# v0_5_1.net
KiCad netlist of a schematic drawn in EAGLE
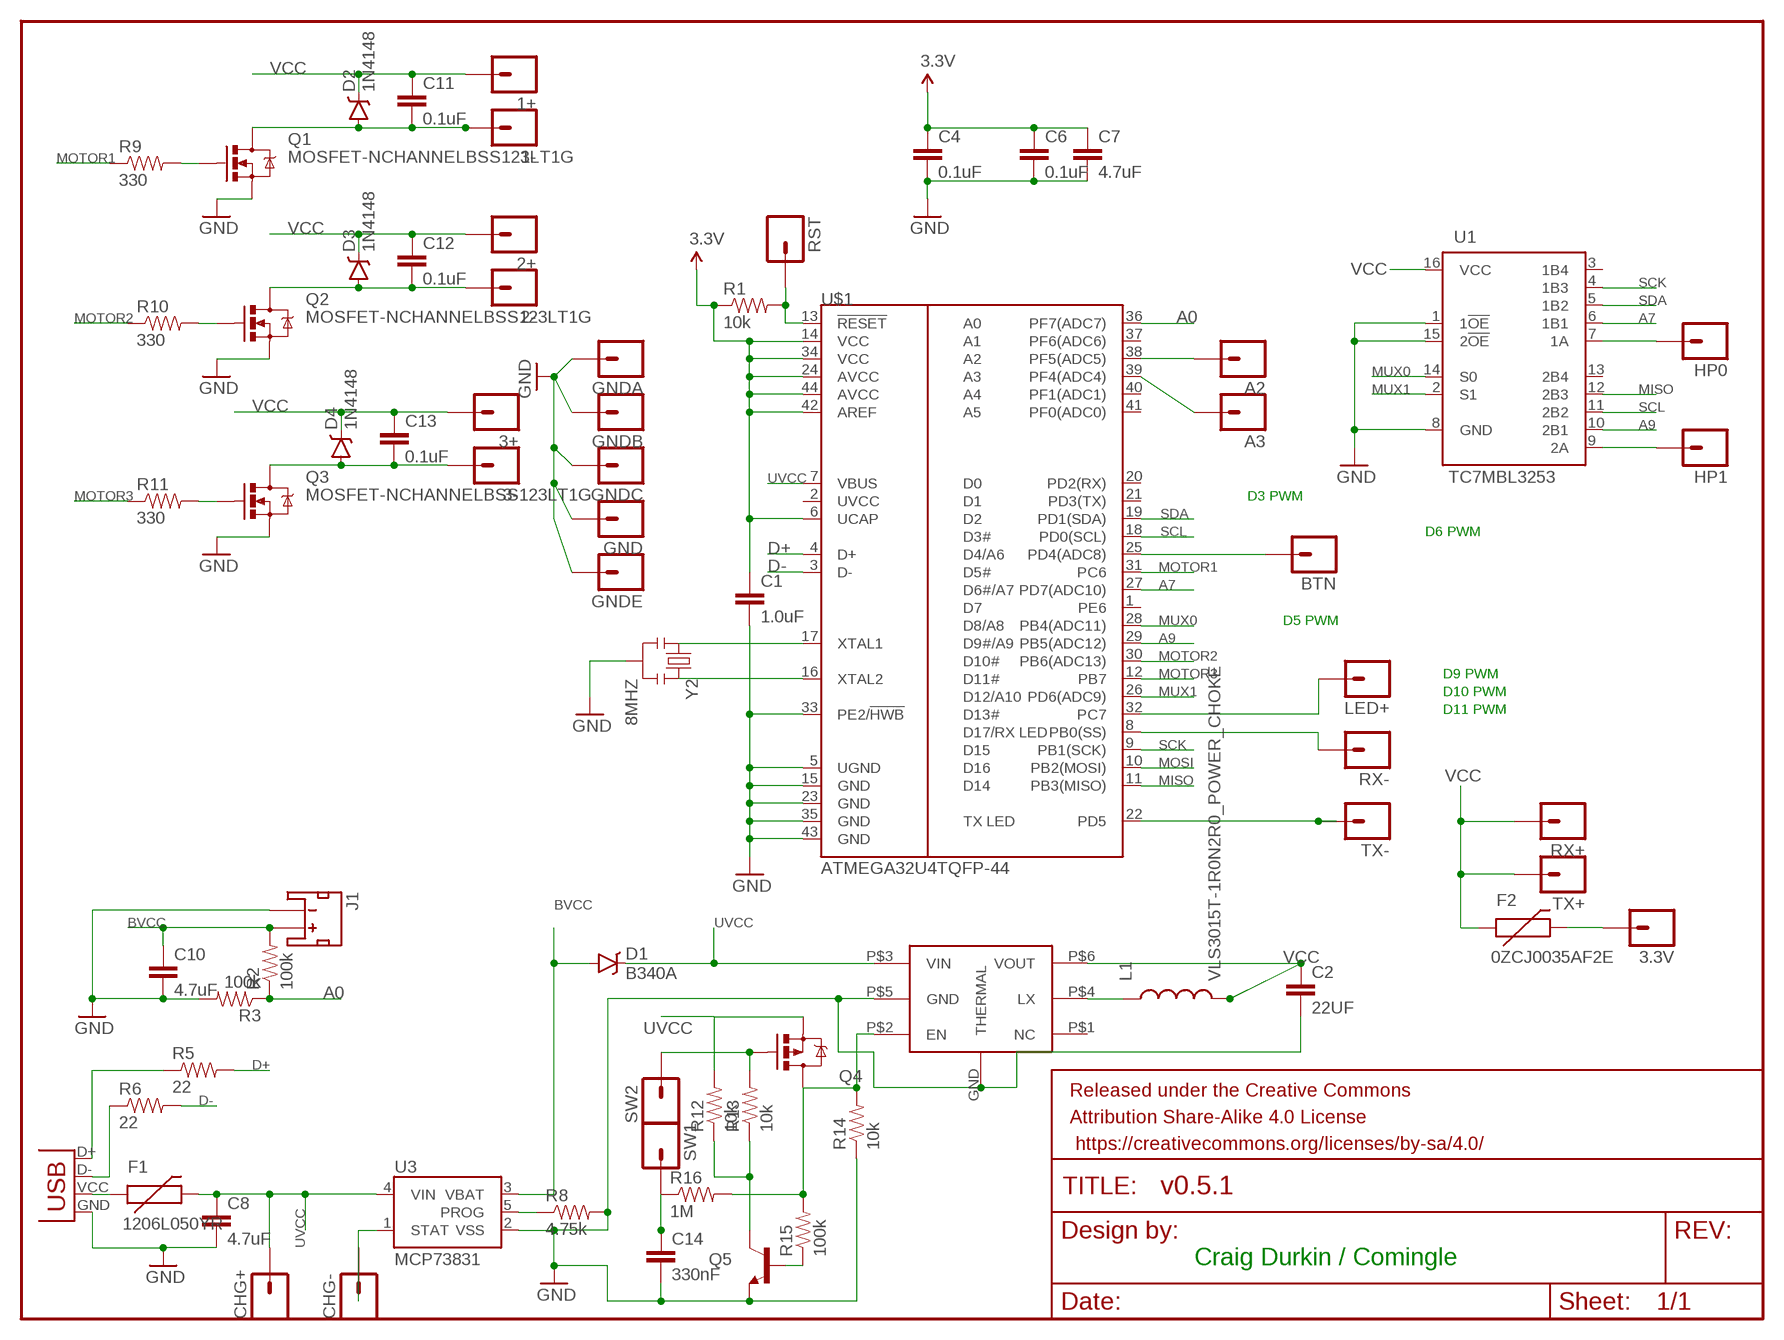
[diagram p0: schematic, sheet 1]

(export (version "E")
  (design (tool "Eeschema 10.0.6"))
  (components
    (comp (ref "1+")
      (value "M01PTH")
      (footprint "eagle-import:1X01")
      (libsource (lib "eagle-import") (part "M01PTH"))
    )
    (comp (ref "1-")
      (value "M01PTH")
      (footprint "eagle-import:1X01")
      (libsource (lib "eagle-import") (part "M01PTH"))
    )
    (comp (ref "2+")
      (value "M01PTH")
      (footprint "eagle-import:1X01")
      (libsource (lib "eagle-import") (part "M01PTH"))
    )
    (comp (ref "2-")
      (value "M01PTH")
      (footprint "eagle-import:1X01")
      (libsource (lib "eagle-import") (part "M01PTH"))
    )
    (comp (ref "3+")
      (value "M01PTH")
      (footprint "eagle-import:1X01")
      (libsource (lib "eagle-import") (part "M01PTH"))
    )
    (comp (ref "3-")
      (value "M01PTH")
      (footprint "eagle-import:1X01")
      (libsource (lib "eagle-import") (part "M01PTH"))
    )
    (comp (ref "3.3V")
      (value "M01PTH")
      (footprint "eagle-import:1X01")
      (libsource (lib "eagle-import") (part "M01PTH"))
    )
    (comp (ref "A2")
      (value "M01PTH")
      (footprint "eagle-import:1X01")
      (libsource (lib "eagle-import") (part "M01PTH"))
    )
    (comp (ref "A3")
      (value "M01PTH")
      (footprint "eagle-import:1X01")
      (libsource (lib "eagle-import") (part "M01PTH"))
    )
    (comp (ref "BTN")
      (value "M01PTH")
      (footprint "eagle-import:1X01")
      (libsource (lib "eagle-import") (part "M01PTH"))
    )
    (comp (ref "C1")
      (value "1.0uF")
      (footprint "eagle-import:0603-CAP")
      (libsource (lib "eagle-import") (part "CAP0603-CAP"))
    )
    (comp (ref "C2")
      (value "22UF")
      (footprint "eagle-import:0805")
      (libsource (lib "eagle-import") (part "v0.4.6_CAP0805"))
    )
    (comp (ref "C4")
      (value "0.1uF")
      (footprint "eagle-import:0603-CAP")
      (libsource (lib "eagle-import") (part "SparkFun-Passives_CAP0603-CAP"))
    )
    (comp (ref "C6")
      (value "0.1uF")
      (footprint "eagle-import:0603-CAP")
      (libsource (lib "eagle-import") (part "SparkFun-Passives_CAP0603-CAP"))
    )
    (comp (ref "C7")
      (value "4.7uF")
      (footprint "eagle-import:0603-CAP")
      (libsource (lib "eagle-import") (part "SparkFun-Passives_CAP0603-CAP"))
    )
    (comp (ref "C8")
      (value "4.7uF")
      (footprint "eagle-import:1206")
      (libsource (lib "eagle-import") (part "SparkFun-Passives_CAP1206"))
    )
    (comp (ref "C10")
      (value "4.7uF")
      (footprint "eagle-import:1206")
      (libsource (lib "eagle-import") (part "SparkFun-Passives_CAP1206"))
    )
    (comp (ref "C11")
      (value "0.1uF")
      (footprint "eagle-import:0603-CAP")
      (libsource (lib "eagle-import") (part "CAP0603-CAP"))
    )
    (comp (ref "C12")
      (value "0.1uF")
      (footprint "eagle-import:0603-CAP")
      (libsource (lib "eagle-import") (part "CAP0603-CAP"))
    )
    (comp (ref "C13")
      (value "0.1uF")
      (footprint "eagle-import:0603-CAP")
      (libsource (lib "eagle-import") (part "CAP0603-CAP"))
    )
    (comp (ref "C14")
      (value "330nF")
      (footprint "eagle-import:0603-CAP")
      (libsource (lib "eagle-import") (part "CAP0603-CAP"))
    )
    (comp (ref "CHG+")
      (value "M01PTH")
      (footprint "eagle-import:1X01")
      (libsource (lib "eagle-import") (part "M01PTH"))
    )
    (comp (ref "CHG-")
      (value "M01PTH")
      (footprint "eagle-import:1X01")
      (libsource (lib "eagle-import") (part "M01PTH"))
    )
    (comp (ref "D1")
      (value "B340A")
      (footprint "eagle-import:SMA-DIODE")
      (libsource (lib "eagle-import") (part "DIODE-SCHOTTKY-B340A"))
    )
    (comp (ref "D2")
      (value "1N4148")
      (footprint "eagle-import:SOD-323")
      (libsource (lib "eagle-import") (part "BAT20JFILM"))
    )
    (comp (ref "D3")
      (value "1N4148")
      (footprint "eagle-import:SOD-323")
      (libsource (lib "eagle-import") (part "BAT20JFILM"))
    )
    (comp (ref "D4")
      (value "1N4148")
      (footprint "eagle-import:SOD-323")
      (libsource (lib "eagle-import") (part "BAT20JFILM"))
    )
    (comp (ref "F1")
      (value "1206L050YR")
      (footprint "eagle-import:PTC-1206")
      (libsource (lib "eagle-import") (part "PTCSMD"))
    )
    (comp (ref "F2")
      (value "0ZCJ0035AF2E")
      (footprint "eagle-import:PTC-1206")
      (libsource (lib "eagle-import") (part "PTCSMD"))
    )
    (comp (ref "FRAME1")
      (value "FRAME-LETTER")
      (footprint "eagle-import:CREATIVE_COMMONS")
      (libsource (lib "eagle-import") (part "FRAME-LETTER"))
    )
    (comp (ref "GND")
      (value "M01PTH")
      (footprint "eagle-import:1X01")
      (libsource (lib "eagle-import") (part "M01PTH"))
    )
    (comp (ref "GNDA")
      (value "M01PTH")
      (footprint "eagle-import:1X01")
      (libsource (lib "eagle-import") (part "M01PTH"))
    )
    (comp (ref "GNDB")
      (value "M01PTH")
      (footprint "eagle-import:1X01")
      (libsource (lib "eagle-import") (part "M01PTH"))
    )
    (comp (ref "GNDC")
      (value "M01PTH")
      (footprint "eagle-import:1X01")
      (libsource (lib "eagle-import") (part "M01PTH"))
    )
    (comp (ref "GNDE")
      (value "M01PTH")
      (footprint "eagle-import:1X01")
      (libsource (lib "eagle-import") (part "M01PTH"))
    )
    (comp (ref "HP0")
      (value "M01PTH")
      (footprint "eagle-import:1X01")
      (libsource (lib "eagle-import") (part "M01PTH"))
    )
    (comp (ref "HP1")
      (value "M01PTH")
      (footprint "eagle-import:1X01")
      (libsource (lib "eagle-import") (part "M01PTH"))
    )
    (comp (ref "J1")
      (value "JST_2MM_MALE")
      (footprint "eagle-import:JST-2-SMD")
      (libsource (lib "eagle-import") (part "JST_2MM_MALE"))
    )
    (comp (ref "JP4")
      (value "USBMICROB-GCT-USB3075")
      (footprint "eagle-import:USB-MICROB-GCT-USB3075")
      (libsource (lib "eagle-import") (part "USBMICROB-GCT-USB3075"))
    )
    (comp (ref "L1")
      (value "VLS3015T-1R0N2R0_POWER_CHOKE")
      (footprint "eagle-import:3MM_POWER_CHOKE")
      (libsource (lib "eagle-import") (part "VLS3015T-1R0N2R0_POWER_CHOKE"))
    )
    (comp (ref "LED+")
      (value "M01PTH")
      (footprint "eagle-import:1X01")
      (libsource (lib "eagle-import") (part "M01PTH"))
    )
    (comp (ref "Q1")
      (value "MOSFET-NCHANNELBSS123LT1G")
      (footprint "eagle-import:SOT23-3")
      (libsource (lib "eagle-import") (part "MOSFET-NCHANNELBSS123LT1G"))
    )
    (comp (ref "Q2")
      (value "MOSFET-NCHANNELBSS123LT1G")
      (footprint "eagle-import:SOT23-3")
      (libsource (lib "eagle-import") (part "MOSFET-NCHANNELBSS123LT1G"))
    )
    (comp (ref "Q3")
      (value "MOSFET-NCHANNELBSS123LT1G")
      (footprint "eagle-import:SOT23-3")
      (libsource (lib "eagle-import") (part "MOSFET-NCHANNELBSS123LT1G"))
    )
    (comp (ref "Q4")
      (value "NTS2101PT1G")
      (footprint "eagle-import:SOT323")
      (libsource (lib "eagle-import") (part "MOSFET-PCHANNELSOT323"))
    )
    (comp (ref "Q5")
      (value "MMBT2222A")
      (footprint "eagle-import:SOT23-3")
      (libsource (lib "eagle-import") (part "TRANSISTOR_NPNMMBT2222A"))
    )
    (comp (ref "R1")
      (value "10k")
      (footprint "eagle-import:0603-RES")
      (libsource (lib "eagle-import") (part "RESISTOR0603-RES"))
    )
    (comp (ref "R2")
      (value "100k")
      (footprint "eagle-import:0603-RES")
      (libsource (lib "eagle-import") (part "RESISTOR0603-RES"))
    )
    (comp (ref "R3")
      (value "100k")
      (footprint "eagle-import:0603-RES")
      (libsource (lib "eagle-import") (part "RESISTOR0603-RES"))
    )
    (comp (ref "R5")
      (value "22")
      (footprint "eagle-import:0603-RES")
      (libsource (lib "eagle-import") (part "RESISTOR0603-RES"))
    )
    (comp (ref "R6")
      (value "22")
      (footprint "eagle-import:0603-RES")
      (libsource (lib "eagle-import") (part "RESISTOR0603-RES"))
    )
    (comp (ref "R8")
      (value "4.75k")
      (footprint "eagle-import:0603-RES")
      (libsource (lib "eagle-import") (part "RESISTOR0603-RES"))
    )
    (comp (ref "R9")
      (value "330")
      (footprint "eagle-import:0603-RES")
      (libsource (lib "eagle-import") (part "RESISTOR0603-RES"))
    )
    (comp (ref "R10")
      (value "330")
      (footprint "eagle-import:0603-RES")
      (libsource (lib "eagle-import") (part "RESISTOR0603-RES"))
    )
    (comp (ref "R11")
      (value "330")
      (footprint "eagle-import:0603-RES")
      (libsource (lib "eagle-import") (part "RESISTOR0603-RES"))
    )
    (comp (ref "R12")
      (value "10k")
      (footprint "eagle-import:0603-RES")
      (libsource (lib "eagle-import") (part "RESISTOR0603-RES"))
    )
    (comp (ref "R13")
      (value "10k")
      (footprint "eagle-import:0603-RES")
      (libsource (lib "eagle-import") (part "RESISTOR0603-RES"))
    )
    (comp (ref "R14")
      (value "10k")
      (footprint "eagle-import:0603-RES")
      (libsource (lib "eagle-import") (part "RESISTOR0603-RES"))
    )
    (comp (ref "R15")
      (value "100k")
      (footprint "eagle-import:0603-RES")
      (libsource (lib "eagle-import") (part "RESISTOR0603-RES"))
    )
    (comp (ref "R16")
      (value "1M")
      (footprint "eagle-import:0603-RES")
      (libsource (lib "eagle-import") (part "RESISTOR0603-RES"))
    )
    (comp (ref "RST")
      (value "M01PTH")
      (footprint "eagle-import:1X01")
      (libsource (lib "eagle-import") (part "M01PTH"))
    )
    (comp (ref "RX+")
      (value "M01PTH")
      (footprint "eagle-import:1X01")
      (libsource (lib "eagle-import") (part "M01PTH"))
    )
    (comp (ref "RX-")
      (value "M01PTH")
      (footprint "eagle-import:1X01")
      (libsource (lib "eagle-import") (part "M01PTH"))
    )
    (comp (ref "SW1")
      (value "M01PTH")
      (footprint "eagle-import:1X01")
      (libsource (lib "eagle-import") (part "M01PTH"))
    )
    (comp (ref "SW2")
      (value "M01PTH")
      (footprint "eagle-import:1X01")
      (libsource (lib "eagle-import") (part "M01PTH"))
    )
    (comp (ref "TX+")
      (value "M01PTH")
      (footprint "eagle-import:1X01")
      (libsource (lib "eagle-import") (part "M01PTH"))
    )
    (comp (ref "TX-")
      (value "M01PTH")
      (footprint "eagle-import:1X01")
      (libsource (lib "eagle-import") (part "M01PTH"))
    )
    (comp (ref "U$1")
      (value "ATMEGA32U4TQFP-44")
      (footprint "eagle-import:TQFP44")
      (libsource (lib "eagle-import") (part "ATMEGA32U4TQFP-44"))
    )
    (comp (ref "U$3")
      (value "SC189")
      (footprint "eagle-import:MLPD-UT6")
      (libsource (lib "eagle-import") (part "SC189"))
    )
    (comp (ref "U1")
      (value "TC7MBL3253")
      (footprint "eagle-import:SSOP16-PRACTICE")
      (libsource (lib "eagle-import") (part "TC7MBL3253"))
    )
    (comp (ref "U3")
      (value "MCP73831")
      (footprint "eagle-import:SOT23-5")
      (libsource (lib "eagle-import") (part "MCP73831"))
    )
    (comp (ref "Y2")
      (value "8MHZ")
      (footprint "eagle-import:RESONATOR-SMD")
      (libsource (lib "eagle-import") (part "RESONATOR8MHZ"))
    )
  )
  (nets
    (net (code "1") (name "/A0") (class "Default")
      (node (ref "R2") (pin "1") (pinfunction "1_1") (pintype "passive"))
      (node (ref "R3") (pin "1") (pinfunction "1_1") (pintype "passive"))
      (node (ref "U$1") (pin "36") (pinfunction "PF7(ADC7)_36") (pintype "bidirectional"))
    )
    (net (code "2") (name "/A7") (class "Default")
      (node (ref "U$1") (pin "27") (pinfunction "PD7(ADC10)_27") (pintype "bidirectional"))
      (node (ref "U1") (pin "6") (pinfunction "1B1_6") (pintype "bidirectional"))
    )
    (net (code "3") (name "/A9") (class "Default")
      (node (ref "U$1") (pin "29") (pinfunction "PB5(ADC12)_29") (pintype "bidirectional"))
      (node (ref "U1") (pin "10") (pinfunction "2B1_10") (pintype "bidirectional"))
    )
    (net (code "4") (name "/BVCC") (class "Default")
      (node (ref "C10") (pin "1") (pinfunction "1_1") (pintype "passive"))
      (node (ref "D1") (pin "A") (pinfunction "A_A") (pintype "passive"))
      (node (ref "J1") (pin "2") (pinfunction "+_2") (pintype "bidirectional"))
      (node (ref "R2") (pin "2") (pinfunction "2_2") (pintype "passive"))
      (node (ref "U3") (pin "3") (pinfunction "VBAT_3") (pintype "power_in"))
    )
    (net (code "5") (name "/D+") (class "Default")
      (node (ref "R5") (pin "2") (pinfunction "2_2") (pintype "passive"))
      (node (ref "U$1") (pin "4") (pinfunction "D+_4") (pintype "bidirectional"))
    )
    (net (code "6") (name "/D-") (class "Default")
      (node (ref "R6") (pin "2") (pinfunction "2_2") (pintype "passive"))
      (node (ref "U$1") (pin "3") (pinfunction "D-_3") (pintype "bidirectional"))
    )
    (net (code "7") (name "/MISO") (class "Default")
      (node (ref "U$1") (pin "11") (pinfunction "PB3(MISO)_11") (pintype "bidirectional"))
      (node (ref "U1") (pin "12") (pinfunction "2B3_12") (pintype "bidirectional"))
    )
    (net (code "8") (name "/MOSI") (class "Default")
      (node (ref "U$1") (pin "10") (pinfunction "PB2(MOSI)_10") (pintype "bidirectional"))
    )
    (net (code "9") (name "/MOTOR1") (class "Default")
      (node (ref "R9") (pin "1") (pinfunction "1_1") (pintype "passive"))
      (node (ref "U$1") (pin "31") (pinfunction "PC6_31") (pintype "bidirectional"))
    )
    (net (code "10") (name "/MOTOR2") (class "Default")
      (node (ref "R10") (pin "1") (pinfunction "1_1") (pintype "passive"))
      (node (ref "U$1") (pin "30") (pinfunction "PB6(ADC13)_30") (pintype "bidirectional"))
    )
    (net (code "11") (name "/MOTOR3") (class "Default")
      (node (ref "R11") (pin "1") (pinfunction "1_1") (pintype "passive"))
      (node (ref "U$1") (pin "12") (pinfunction "PB7_12") (pintype "bidirectional"))
    )
    (net (code "12") (name "/MUX0") (class "Default")
      (node (ref "U$1") (pin "28") (pinfunction "PB4(ADC11)_28") (pintype "bidirectional"))
      (node (ref "U1") (pin "14") (pinfunction "S0_14") (pintype "bidirectional"))
    )
    (net (code "13") (name "/MUX1") (class "Default")
      (node (ref "U$1") (pin "26") (pinfunction "PD6(ADC9)_26") (pintype "bidirectional"))
      (node (ref "U1") (pin "2") (pinfunction "S1_2") (pintype "bidirectional"))
    )
    (net (code "14") (name "/SCK") (class "Default")
      (node (ref "U$1") (pin "9") (pinfunction "PB1(SCK)_9") (pintype "bidirectional"))
      (node (ref "U1") (pin "4") (pinfunction "1B3_4") (pintype "bidirectional"))
    )
    (net (code "15") (name "/SCL") (class "Default")
      (node (ref "U$1") (pin "18") (pinfunction "PD0(SCL)_18") (pintype "bidirectional"))
      (node (ref "U1") (pin "11") (pinfunction "2B2_11") (pintype "bidirectional"))
    )
    (net (code "16") (name "/SDA") (class "Default")
      (node (ref "U$1") (pin "19") (pinfunction "PD1(SDA)_19") (pintype "bidirectional"))
      (node (ref "U1") (pin "5") (pinfunction "1B2_5") (pintype "bidirectional"))
    )
    (net (code "17") (name "/UVCC") (class "Default")
      (node (ref "C8") (pin "1") (pinfunction "1_1") (pintype "passive"))
      (node (ref "CHG+") (pin "1") (pinfunction "1_1") (pintype "passive"))
      (node (ref "D1") (pin "C") (pinfunction "C_C") (pintype "passive"))
      (node (ref "F1") (pin "2") (pinfunction "2_2") (pintype "bidirectional"))
      (node (ref "Q4") (pin "2") (pinfunction "S_2") (pintype "passive"))
      (node (ref "R12") (pin "2") (pinfunction "2_2") (pintype "passive"))
      (node (ref "U$1") (pin "7") (pinfunction "VBUS_7") (pintype "bidirectional"))
      (node (ref "U$3") (pin "P$3") (pinfunction "VIN_P$3") (pintype "power_in"))
      (node (ref "U3") (pin "4") (pinfunction "VIN_4") (pintype "power_in"))
    )
    (net (code "18") (name "3.3V") (class "Default")
      (node (ref "1+") (pin "1") (pinfunction "1_1") (pintype "passive"))
      (node (ref "2+") (pin "1") (pinfunction "1_1") (pintype "passive"))
      (node (ref "3+") (pin "1") (pinfunction "1_1") (pintype "passive"))
      (node (ref "C1") (pin "1") (pinfunction "1_1") (pintype "passive"))
      (node (ref "C11") (pin "1") (pinfunction "1_1") (pintype "passive"))
      (node (ref "C12") (pin "1") (pinfunction "1_1") (pintype "passive"))
      (node (ref "C13") (pin "1") (pinfunction "1_1") (pintype "passive"))
      (node (ref "C2") (pin "1") (pinfunction "1_1") (pintype "passive"))
      (node (ref "C4") (pin "1") (pinfunction "1_1") (pintype "passive"))
      (node (ref "C6") (pin "1") (pinfunction "1_1") (pintype "passive"))
      (node (ref "C7") (pin "1") (pinfunction "1_1") (pintype "passive"))
      (node (ref "D2") (pin "C") (pinfunction "C_C") (pintype "passive"))
      (node (ref "D3") (pin "C") (pinfunction "C_C") (pintype "passive"))
      (node (ref "D4") (pin "C") (pinfunction "C_C") (pintype "passive"))
      (node (ref "F2") (pin "1") (pinfunction "1_1") (pintype "bidirectional"))
      (node (ref "L1") (pin "2") (pinfunction "2_2") (pintype "passive"))
      (node (ref "R1") (pin "1") (pinfunction "1_1") (pintype "passive"))
      (node (ref "RX+") (pin "1") (pinfunction "1_1") (pintype "passive"))
      (node (ref "TX+") (pin "1") (pinfunction "1_1") (pintype "passive"))
      (node (ref "U$1") (pin "14") (pinfunction "VCC_14") (pintype "bidirectional"))
      (node (ref "U$1") (pin "24") (pinfunction "AVCC_24") (pintype "bidirectional"))
      (node (ref "U$1") (pin "34") (pinfunction "VCC_34") (pintype "bidirectional"))
      (node (ref "U$1") (pin "42") (pinfunction "AREF_42") (pintype "bidirectional"))
      (node (ref "U$1") (pin "44") (pinfunction "AVCC_44") (pintype "bidirectional"))
      (node (ref "U$1") (pin "6") (pinfunction "UCAP_6") (pintype "bidirectional"))
      (node (ref "U$3") (pin "P$6") (pinfunction "VOUT_P$6") (pintype "output"))
      (node (ref "U1") (pin "16") (pinfunction "VCC_16") (pintype "power_in"))
    )
    (net (code "19") (name "GND") (class "Default")
      (node (ref "C1") (pin "2") (pinfunction "2_2") (pintype "passive"))
      (node (ref "C10") (pin "2") (pinfunction "2_2") (pintype "passive"))
      (node (ref "C14") (pin "2") (pinfunction "2_2") (pintype "passive"))
      (node (ref "C2") (pin "2") (pinfunction "2_2") (pintype "passive"))
      (node (ref "C4") (pin "2") (pinfunction "2_2") (pintype "passive"))
      (node (ref "C6") (pin "2") (pinfunction "2_2") (pintype "passive"))
      (node (ref "C7") (pin "2") (pinfunction "2_2") (pintype "passive"))
      (node (ref "C8") (pin "2") (pinfunction "2_2") (pintype "passive"))
      (node (ref "GND") (pin "1") (pinfunction "1_1") (pintype "passive"))
      (node (ref "GNDA") (pin "1") (pinfunction "1_1") (pintype "passive"))
      (node (ref "GNDB") (pin "1") (pinfunction "1_1") (pintype "passive"))
      (node (ref "GNDC") (pin "1") (pinfunction "1_1") (pintype "passive"))
      (node (ref "GNDE") (pin "1") (pinfunction "1_1") (pintype "passive"))
      (node (ref "J1") (pin "1") (pinfunction "-_1") (pintype "bidirectional"))
      (node (ref "JP4") (pin "GND") (pinfunction "GND_GND") (pintype "bidirectional"))
      (node (ref "Q1") (pin "2") (pinfunction "S_2") (pintype "passive"))
      (node (ref "Q2") (pin "2") (pinfunction "S_2") (pintype "passive"))
      (node (ref "Q3") (pin "2") (pinfunction "S_2") (pintype "passive"))
      (node (ref "Q5") (pin "2") (pinfunction "E_2") (pintype "passive"))
      (node (ref "R14") (pin "1") (pinfunction "1_1") (pintype "passive"))
      (node (ref "R3") (pin "2") (pinfunction "2_2") (pintype "passive"))
      (node (ref "R8") (pin "2") (pinfunction "2_2") (pintype "passive"))
      (node (ref "U$1") (pin "15") (pinfunction "GND_15") (pintype "bidirectional"))
      (node (ref "U$1") (pin "23") (pinfunction "GND_23") (pintype "bidirectional"))
      (node (ref "U$1") (pin "33") (pinfunction "PE2/~{HWB}_33") (pintype "bidirectional"))
      (node (ref "U$1") (pin "35") (pinfunction "GND_35") (pintype "bidirectional"))
      (node (ref "U$1") (pin "43") (pinfunction "GND_43") (pintype "bidirectional"))
      (node (ref "U$1") (pin "5") (pinfunction "UGND_5") (pintype "bidirectional"))
      (node (ref "U$3") (pin "GND") (pinfunction "THERMAL_GND") (pintype "power_in"))
      (node (ref "U$3") (pin "P$5") (pinfunction "GND_P$5") (pintype "power_in"))
      (node (ref "U1") (pin "1") (pinfunction "1~{OE}_1") (pintype "input"))
      (node (ref "U1") (pin "15") (pinfunction "2~{OE}_15") (pintype "input"))
      (node (ref "U1") (pin "8") (pinfunction "GND_8") (pintype "power_in"))
      (node (ref "U3") (pin "2") (pinfunction "VSS_2") (pintype "power_in"))
      (node (ref "Y2") (pin "2") (pinfunction "2_2") (pintype "passive"))
    )
    (net (code "20") (name "Net-(3.3V-Pad1)") (class "Default")
      (node (ref "3.3V") (pin "1") (pinfunction "1_1") (pintype "passive"))
      (node (ref "F2") (pin "2") (pinfunction "2_2") (pintype "bidirectional"))
    )
    (net (code "21") (name "Net-(C14-Pad1)") (class "Default")
      (node (ref "C14") (pin "1") (pinfunction "1_1") (pintype "passive"))
      (node (ref "R16") (pin "1") (pinfunction "1_1") (pintype "passive"))
      (node (ref "SW1") (pin "1") (pinfunction "1_1") (pintype "passive"))
    )
    (net (code "22") (name "Net-(JP4-PadD+)") (class "Default")
      (node (ref "JP4") (pin "D+") (pinfunction "D+_D+") (pintype "bidirectional"))
      (node (ref "R5") (pin "1") (pinfunction "1_1") (pintype "passive"))
    )
    (net (code "23") (name "Net-(JP4-PadD-)") (class "Default")
      (node (ref "JP4") (pin "D-") (pinfunction "D-_D-") (pintype "bidirectional"))
      (node (ref "R6") (pin "1") (pinfunction "1_1") (pintype "passive"))
    )
    (net (code "24") (name "Net-(JP4-VBUS)") (class "Default")
      (node (ref "F1") (pin "1") (pinfunction "1_1") (pintype "bidirectional"))
      (node (ref "JP4") (pin "VCC") (pinfunction "VBUS_VCC") (pintype "bidirectional"))
    )
    (net (code "25") (name "Net-(Q1-D)") (class "Default")
      (node (ref "1-") (pin "1") (pinfunction "1_1") (pintype "passive"))
      (node (ref "C11") (pin "2") (pinfunction "2_2") (pintype "passive"))
      (node (ref "D2") (pin "A") (pinfunction "A_A") (pintype "passive"))
      (node (ref "Q1") (pin "3") (pinfunction "D_3") (pintype "passive"))
    )
    (net (code "26") (name "Net-(Q1-G)") (class "Default")
      (node (ref "Q1") (pin "1") (pinfunction "G_1") (pintype "passive"))
      (node (ref "R9") (pin "2") (pinfunction "2_2") (pintype "passive"))
    )
    (net (code "27") (name "Net-(Q2-D)") (class "Default")
      (node (ref "2-") (pin "1") (pinfunction "1_1") (pintype "passive"))
      (node (ref "C12") (pin "2") (pinfunction "2_2") (pintype "passive"))
      (node (ref "D3") (pin "A") (pinfunction "A_A") (pintype "passive"))
      (node (ref "Q2") (pin "3") (pinfunction "D_3") (pintype "passive"))
    )
    (net (code "28") (name "Net-(Q2-G)") (class "Default")
      (node (ref "Q2") (pin "1") (pinfunction "G_1") (pintype "passive"))
      (node (ref "R10") (pin "2") (pinfunction "2_2") (pintype "passive"))
    )
    (net (code "29") (name "Net-(Q3-D)") (class "Default")
      (node (ref "3-") (pin "1") (pinfunction "1_1") (pintype "passive"))
      (node (ref "C13") (pin "2") (pinfunction "2_2") (pintype "passive"))
      (node (ref "D4") (pin "A") (pinfunction "A_A") (pintype "passive"))
      (node (ref "Q3") (pin "3") (pinfunction "D_3") (pintype "passive"))
    )
    (net (code "30") (name "Net-(Q3-G)") (class "Default")
      (node (ref "Q3") (pin "1") (pinfunction "G_1") (pintype "passive"))
      (node (ref "R11") (pin "2") (pinfunction "2_2") (pintype "passive"))
    )
    (net (code "31") (name "Net-(Q4-D)") (class "Default")
      (node (ref "Q4") (pin "3") (pinfunction "D_3") (pintype "passive"))
      (node (ref "R14") (pin "2") (pinfunction "2_2") (pintype "passive"))
      (node (ref "R15") (pin "2") (pinfunction "2_2") (pintype "passive"))
      (node (ref "R16") (pin "2") (pinfunction "2_2") (pintype "passive"))
      (node (ref "U$3") (pin "P$2") (pinfunction "EN_P$2") (pintype "input"))
    )
    (net (code "32") (name "Net-(Q4-G)") (class "Default")
      (node (ref "Q4") (pin "1") (pinfunction "G_1") (pintype "passive"))
      (node (ref "R13") (pin "2") (pinfunction "2_2") (pintype "passive"))
      (node (ref "SW2") (pin "1") (pinfunction "1_1") (pintype "passive"))
    )
    (net (code "33") (name "Net-(Q5-B)") (class "Default")
      (node (ref "Q5") (pin "1") (pinfunction "B_1") (pintype "passive"))
      (node (ref "R15") (pin "1") (pinfunction "1_1") (pintype "passive"))
    )
    (net (code "34") (name "Net-(Q5-C)") (class "Default")
      (node (ref "Q5") (pin "3") (pinfunction "C_3") (pintype "passive"))
      (node (ref "R12") (pin "1") (pinfunction "1_1") (pintype "passive"))
      (node (ref "R13") (pin "1") (pinfunction "1_1") (pintype "passive"))
    )
    (net (code "35") (name "Net-(U$1-PB0(SS))") (class "Default")
      (node (ref "RX-") (pin "1") (pinfunction "1_1") (pintype "passive"))
      (node (ref "U$1") (pin "8") (pinfunction "PB0(SS)_8") (pintype "bidirectional"))
    )
    (net (code "36") (name "Net-(U$1-PC7)") (class "Default")
      (node (ref "LED+") (pin "1") (pinfunction "1_1") (pintype "passive"))
      (node (ref "U$1") (pin "32") (pinfunction "PC7_32") (pintype "bidirectional"))
    )
    (net (code "37") (name "Net-(U$1-PD4(ADC8))") (class "Default")
      (node (ref "BTN") (pin "1") (pinfunction "1_1") (pintype "passive"))
      (node (ref "U$1") (pin "25") (pinfunction "PD4(ADC8)_25") (pintype "bidirectional"))
    )
    (net (code "38") (name "Net-(U$1-PD5)") (class "Default")
      (node (ref "TX-") (pin "1") (pinfunction "1_1") (pintype "passive"))
      (node (ref "U$1") (pin "22") (pinfunction "PD5_22") (pintype "bidirectional"))
    )
    (net (code "39") (name "Net-(U$1-PF4(ADC4))") (class "Default")
      (node (ref "A3") (pin "1") (pinfunction "1_1") (pintype "passive"))
      (node (ref "U$1") (pin "39") (pinfunction "PF4(ADC4)_39") (pintype "bidirectional"))
    )
    (net (code "40") (name "Net-(U$1-PF5(ADC5))") (class "Default")
      (node (ref "A2") (pin "1") (pinfunction "1_1") (pintype "passive"))
      (node (ref "U$1") (pin "38") (pinfunction "PF5(ADC5)_38") (pintype "bidirectional"))
    )
    (net (code "41") (name "Net-(U$1-XTAL1)") (class "Default")
      (node (ref "U$1") (pin "17") (pinfunction "XTAL1_17") (pintype "bidirectional"))
      (node (ref "Y2") (pin "1") (pinfunction "1_1") (pintype "passive"))
    )
    (net (code "42") (name "Net-(U$1-XTAL2)") (class "Default")
      (node (ref "U$1") (pin "16") (pinfunction "XTAL2_16") (pintype "bidirectional"))
      (node (ref "Y2") (pin "3") (pinfunction "3_3") (pintype "passive"))
    )
    (net (code "43") (name "Net-(U$1-~{RESET})") (class "Default")
      (node (ref "R1") (pin "2") (pinfunction "2_2") (pintype "passive"))
      (node (ref "RST") (pin "1") (pinfunction "1_1") (pintype "passive"))
      (node (ref "U$1") (pin "13") (pinfunction "~{RESET}_13") (pintype "bidirectional"))
    )
    (net (code "44") (name "Net-(U$3-LX)") (class "Default")
      (node (ref "L1") (pin "1") (pinfunction "1_1") (pintype "passive"))
      (node (ref "U$3") (pin "P$4") (pinfunction "LX_P$4") (pintype "passive"))
    )
    (net (code "45") (name "Net-(U1-1A)") (class "Default")
      (node (ref "HP0") (pin "1") (pinfunction "1_1") (pintype "passive"))
      (node (ref "U1") (pin "7") (pinfunction "1A_7") (pintype "bidirectional"))
    )
    (net (code "46") (name "Net-(U1-2A)") (class "Default")
      (node (ref "HP1") (pin "1") (pinfunction "1_1") (pintype "passive"))
      (node (ref "U1") (pin "9") (pinfunction "2A_9") (pintype "bidirectional"))
    )
    (net (code "47") (name "Net-(U3-PROG)") (class "Default")
      (node (ref "R8") (pin "1") (pinfunction "1_1") (pintype "passive"))
      (node (ref "U3") (pin "5") (pinfunction "PROG_5") (pintype "bidirectional"))
    )
    (net (code "48") (name "Net-(U3-STAT)") (class "Default")
      (node (ref "CHG-") (pin "1") (pinfunction "1_1") (pintype "passive"))
      (node (ref "U3") (pin "1") (pinfunction "STAT_1") (pintype "output"))
    )
    (net (code "49") (name "unconnected-(J1-PAD1-PadNC1)") (class "Default")
      (node (ref "J1") (pin "NC1") (pinfunction "PAD1_NC1") (pintype "bidirectional"))
    )
    (net (code "50") (name "unconnected-(J1-PAD2-PadNC2)") (class "Default")
      (node (ref "J1") (pin "NC2") (pinfunction "PAD2_NC2") (pintype "bidirectional"))
    )
    (net (code "51") (name "unconnected-(U$1-PD2(RX)-Pad20)") (class "Default")
      (node (ref "U$1") (pin "20") (pinfunction "PD2(RX)_20") (pintype "bidirectional"))
    )
    (net (code "52") (name "unconnected-(U$1-PD3(TX)-Pad21)") (class "Default")
      (node (ref "U$1") (pin "21") (pinfunction "PD3(TX)_21") (pintype "bidirectional"))
    )
    (net (code "53") (name "unconnected-(U$1-PE6-Pad1)") (class "Default")
      (node (ref "U$1") (pin "1") (pinfunction "PE6_1") (pintype "bidirectional"))
    )
    (net (code "54") (name "unconnected-(U$1-PF0(ADC0)-Pad41)") (class "Default")
      (node (ref "U$1") (pin "41") (pinfunction "PF0(ADC0)_41") (pintype "bidirectional"))
    )
    (net (code "55") (name "unconnected-(U$1-PF1(ADC1)-Pad40)") (class "Default")
      (node (ref "U$1") (pin "40") (pinfunction "PF1(ADC1)_40") (pintype "bidirectional"))
    )
    (net (code "56") (name "unconnected-(U$1-PF6(ADC6)-Pad37)") (class "Default")
      (node (ref "U$1") (pin "37") (pinfunction "PF6(ADC6)_37") (pintype "bidirectional"))
    )
    (net (code "57") (name "unconnected-(U$1-UVCC-Pad2)") (class "Default")
      (node (ref "U$1") (pin "2") (pinfunction "UVCC_2") (pintype "bidirectional"))
    )
    (net (code "58") (name "unconnected-(U$3-NC-PadP$1)") (class "Default")
      (node (ref "U$3") (pin "P$1") (pinfunction "NC_P$1") (pintype "no_connect"))
    )
    (net (code "59") (name "unconnected-(U1-1B4-Pad3)") (class "Default")
      (node (ref "U1") (pin "3") (pinfunction "1B4_3") (pintype "bidirectional"))
    )
    (net (code "60") (name "unconnected-(U1-2B4-Pad13)") (class "Default")
      (node (ref "U1") (pin "13") (pinfunction "2B4_13") (pintype "bidirectional"))
    )
  )
)
